# Amplificador_Clase_A.net
KiCad netlist of a schematic drawn in EAGLE
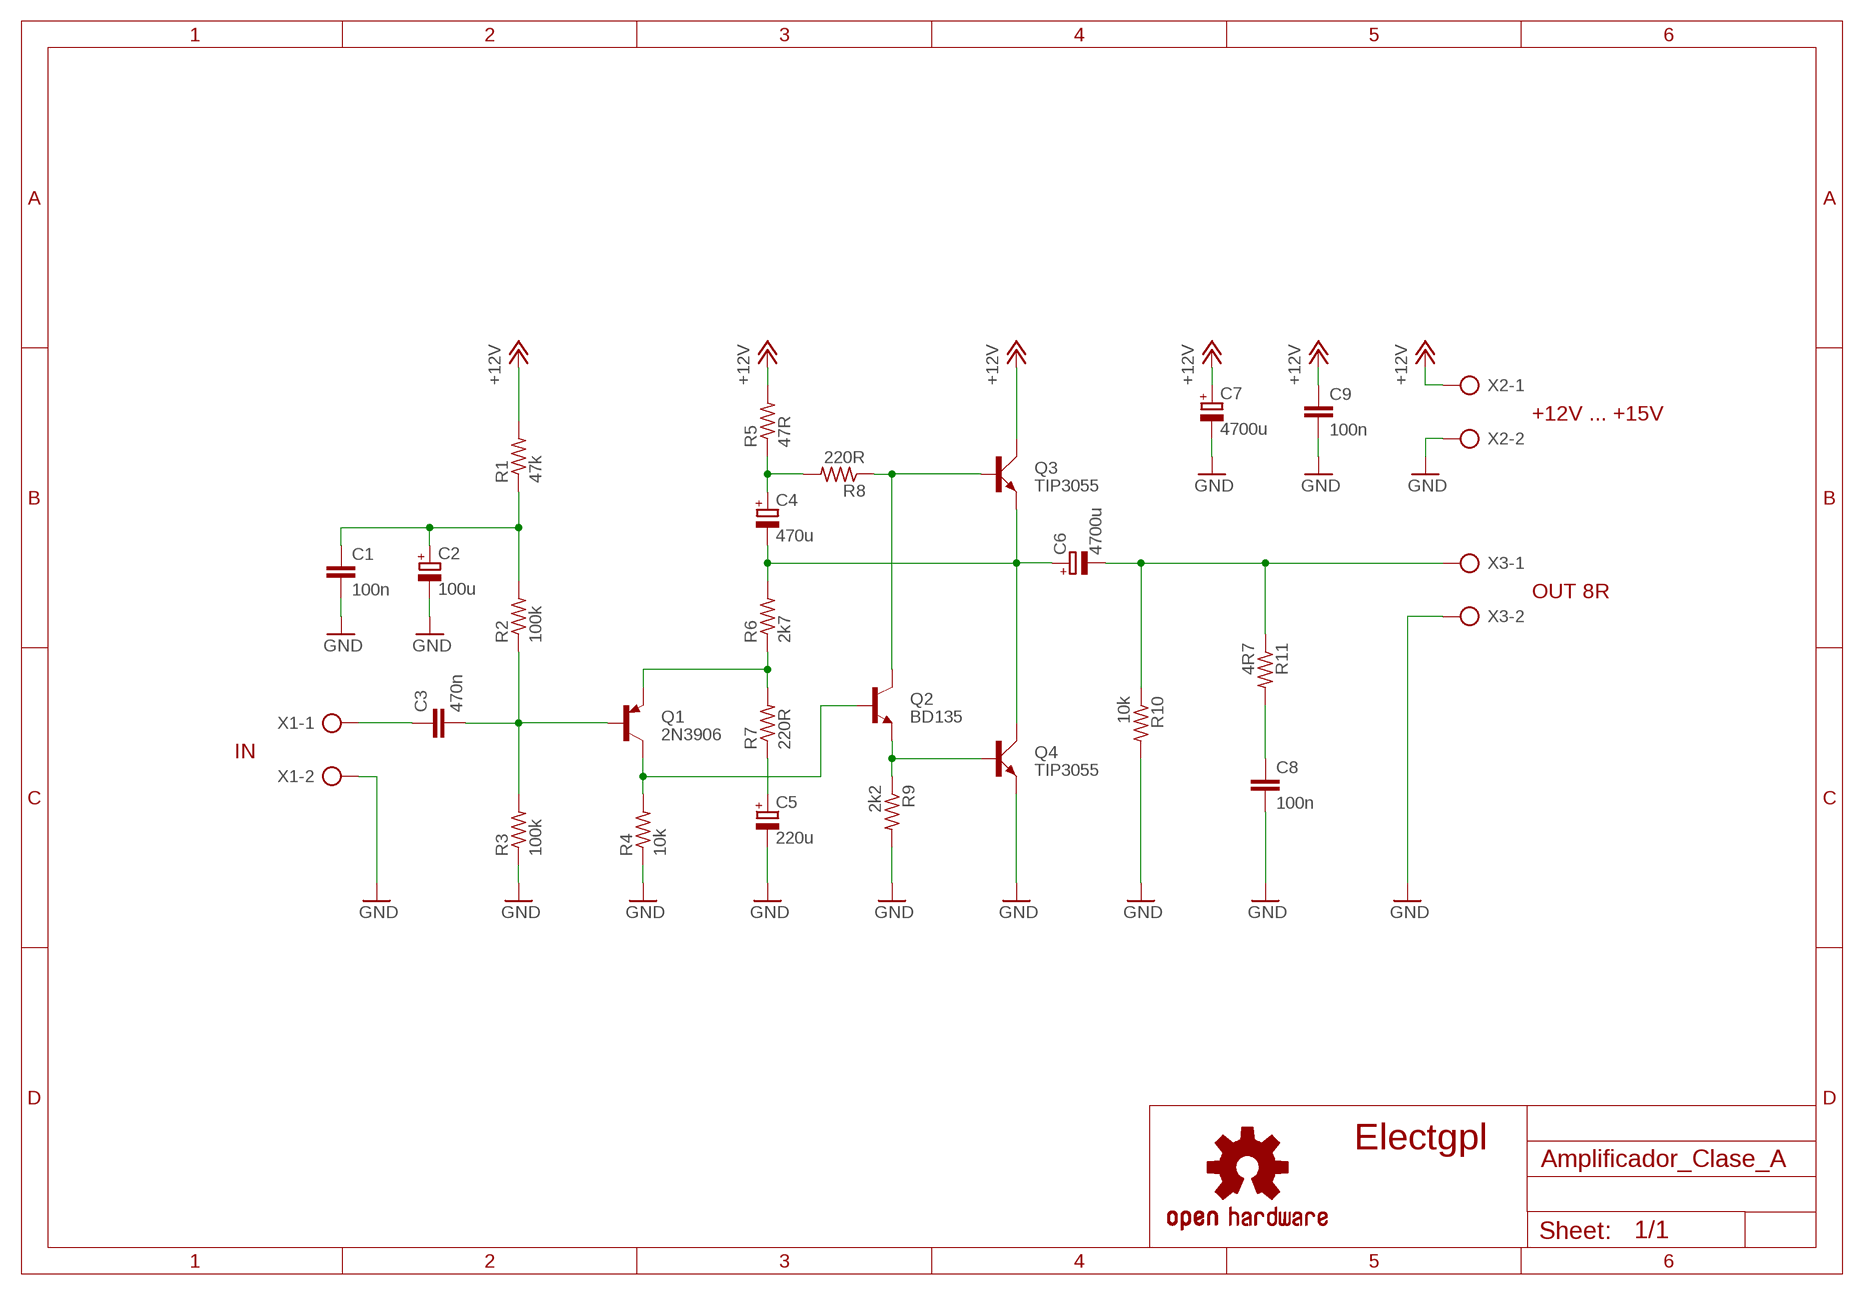
[diagram p0: schematic, sheet 1]

(export (version "E")
  (design (tool "Eeschema 10.0.6"))
  (components
    (comp (ref "C1")
      (value "100n")
      (footprint "eagle-import:C050-024X044")
      (libsource (lib "eagle-import") (part "C-EU050-024X044"))
    )
    (comp (ref "C2")
      (value "100u")
      (footprint "eagle-import:E3,5-10")
      (libsource (lib "eagle-import") (part "CPOL-EUE3.5-10"))
    )
    (comp (ref "C3")
      (value "470n")
      (footprint "eagle-import:C050-024X044")
      (libsource (lib "eagle-import") (part "C-EU050-024X044"))
    )
    (comp (ref "C4")
      (value "470u")
      (footprint "eagle-import:E7,5-16")
      (libsource (lib "eagle-import") (part "CPOL-EUE7.5-16"))
    )
    (comp (ref "C5")
      (value "220u")
      (footprint "eagle-import:E3,5-10")
      (libsource (lib "eagle-import") (part "CPOL-EUE3.5-10"))
    )
    (comp (ref "C6")
      (value "4700u")
      (footprint "eagle-import:E7,5-16")
      (libsource (lib "eagle-import") (part "CPOL-EUE7.5-16"))
    )
    (comp (ref "C7")
      (value "4700u")
      (footprint "eagle-import:E7,5-16")
      (libsource (lib "eagle-import") (part "CPOL-EUE7.5-16"))
    )
    (comp (ref "C8")
      (value "100n")
      (footprint "eagle-import:C050-024X044")
      (libsource (lib "eagle-import") (part "C-EU050-024X044"))
    )
    (comp (ref "C9")
      (value "100n")
      (footprint "eagle-import:C050-024X044")
      (libsource (lib "eagle-import") (part "C-EU050-024X044"))
    )
    (comp (ref "LOGO1")
      (value "OSHW-LOGOM")
      (footprint "eagle-import:OSHW-LOGO-M")
      (libsource (lib "eagle-import") (part "OSHW-LOGOM"))
    )
    (comp (ref "Q1")
      (value "2N3906")
      (footprint "eagle-import:TO92-EBC")
      (libsource (lib "eagle-import") (part "-PNP-TO92-EBC2N3906"))
    )
    (comp (ref "Q2")
      (value "BD135")
      (footprint "eagle-import:TO126V")
      (libsource (lib "eagle-import") (part "-NPN-TO126V"))
    )
    (comp (ref "Q3")
      (value "TIP3055")
      (footprint "eagle-import:TOP3AV")
      (libsource (lib "eagle-import") (part "TIP3055"))
    )
    (comp (ref "Q4")
      (value "TIP3055")
      (footprint "eagle-import:TOP3AV")
      (libsource (lib "eagle-import") (part "TIP3055"))
    )
    (comp (ref "R1")
      (value "47k")
      (footprint "eagle-import:0207_12")
      (libsource (lib "eagle-import") (part "R-US_0207/12"))
    )
    (comp (ref "R2")
      (value "100k")
      (footprint "eagle-import:0207_12")
      (libsource (lib "eagle-import") (part "R-US_0207/12"))
    )
    (comp (ref "R3")
      (value "100k")
      (footprint "eagle-import:0207_12")
      (libsource (lib "eagle-import") (part "R-US_0207/12"))
    )
    (comp (ref "R4")
      (value "10k")
      (footprint "eagle-import:0207_12")
      (libsource (lib "eagle-import") (part "R-US_0207/12"))
    )
    (comp (ref "R5")
      (value "47R")
      (footprint "eagle-import:0207_12")
      (libsource (lib "eagle-import") (part "R-US_0207/12"))
    )
    (comp (ref "R6")
      (value "2k7")
      (footprint "eagle-import:0207_12")
      (libsource (lib "eagle-import") (part "R-US_0207/12"))
    )
    (comp (ref "R7")
      (value "220R")
      (footprint "eagle-import:0207_12")
      (libsource (lib "eagle-import") (part "R-US_0207/12"))
    )
    (comp (ref "R8")
      (value "220R")
      (footprint "eagle-import:0207_12")
      (libsource (lib "eagle-import") (part "R-US_0207/12"))
    )
    (comp (ref "R9")
      (value "2k2")
      (footprint "eagle-import:0207_12")
      (libsource (lib "eagle-import") (part "R-US_0207/12"))
    )
    (comp (ref "R10")
      (value "10k")
      (footprint "eagle-import:0207_12")
      (libsource (lib "eagle-import") (part "R-US_0207/12"))
    )
    (comp (ref "R11")
      (value "4R7")
      (footprint "eagle-import:0207_12")
      (libsource (lib "eagle-import") (part "R-US_0207/12"))
    )
    (comp (ref "X1")
      (value "AK500/2")
      (footprint "eagle-import:AK500_2")
      (libsource (lib "eagle-import") (part "AK500/2"))
    )
    (comp (ref "X2")
      (value "AK500/2")
      (footprint "eagle-import:AK500_2")
      (libsource (lib "eagle-import") (part "AK500/2"))
    )
    (comp (ref "X3")
      (value "AK500/2")
      (footprint "eagle-import:AK500_2")
      (libsource (lib "eagle-import") (part "AK500/2"))
    )
  )
  (nets
    (net (code "1") (name "+12V") (class "Default")
      (node (ref "C7") (pin "+") (pinfunction "+_+") (pintype "passive"))
      (node (ref "C9") (pin "1") (pinfunction "1_1") (pintype "passive"))
      (node (ref "Q3") (pin "C") (pinfunction "C_C") (pintype "passive"))
      (node (ref "R1") (pin "2") (pinfunction "2_2") (pintype "passive"))
      (node (ref "R5") (pin "2") (pinfunction "2_2") (pintype "passive"))
      (node (ref "X2") (pin "1") (pinfunction "KL_1") (pintype "passive"))
    )
    (net (code "2") (name "GND") (class "Default")
      (node (ref "C1") (pin "2") (pinfunction "2_2") (pintype "passive"))
      (node (ref "C2") (pin "-") (pinfunction "-_-") (pintype "passive"))
      (node (ref "C5") (pin "-") (pinfunction "-_-") (pintype "passive"))
      (node (ref "C7") (pin "-") (pinfunction "-_-") (pintype "passive"))
      (node (ref "C8") (pin "2") (pinfunction "2_2") (pintype "passive"))
      (node (ref "C9") (pin "2") (pinfunction "2_2") (pintype "passive"))
      (node (ref "Q4") (pin "E") (pinfunction "E_E") (pintype "passive"))
      (node (ref "R10") (pin "2") (pinfunction "2_2") (pintype "passive"))
      (node (ref "R3") (pin "1") (pinfunction "1_1") (pintype "passive"))
      (node (ref "R4") (pin "1") (pinfunction "1_1") (pintype "passive"))
      (node (ref "R9") (pin "2") (pinfunction "2_2") (pintype "passive"))
      (node (ref "X1") (pin "2") (pinfunction "KL_2") (pintype "passive"))
      (node (ref "X2") (pin "2") (pinfunction "KL_2") (pintype "passive"))
      (node (ref "X3") (pin "2") (pinfunction "KL_2") (pintype "passive"))
    )
    (net (code "3") (name "Net-(C1-Pad1)") (class "Default")
      (node (ref "C1") (pin "1") (pinfunction "1_1") (pintype "passive"))
      (node (ref "C2") (pin "+") (pinfunction "+_+") (pintype "passive"))
      (node (ref "R1") (pin "1") (pinfunction "1_1") (pintype "passive"))
      (node (ref "R2") (pin "2") (pinfunction "2_2") (pintype "passive"))
    )
    (net (code "4") (name "Net-(C3-Pad2)") (class "Default")
      (node (ref "C3") (pin "2") (pinfunction "2_2") (pintype "passive"))
      (node (ref "Q1") (pin "B") (pinfunction "B_B") (pintype "passive"))
      (node (ref "R2") (pin "1") (pinfunction "1_1") (pintype "passive"))
      (node (ref "R3") (pin "2") (pinfunction "2_2") (pintype "passive"))
    )
    (net (code "5") (name "Net-(C4-Pad+)") (class "Default")
      (node (ref "C4") (pin "+") (pinfunction "+_+") (pintype "passive"))
      (node (ref "R5") (pin "1") (pinfunction "1_1") (pintype "passive"))
      (node (ref "R8") (pin "2") (pinfunction "2_2") (pintype "passive"))
    )
    (net (code "6") (name "Net-(C4-Pad-)") (class "Default")
      (node (ref "C4") (pin "-") (pinfunction "-_-") (pintype "passive"))
      (node (ref "C6") (pin "+") (pinfunction "+_+") (pintype "passive"))
      (node (ref "Q3") (pin "E") (pinfunction "E_E") (pintype "passive"))
      (node (ref "Q4") (pin "C") (pinfunction "C_C") (pintype "passive"))
      (node (ref "R6") (pin "2") (pinfunction "2_2") (pintype "passive"))
    )
    (net (code "7") (name "Net-(C5-Pad+)") (class "Default")
      (node (ref "C5") (pin "+") (pinfunction "+_+") (pintype "passive"))
      (node (ref "R7") (pin "1") (pinfunction "1_1") (pintype "passive"))
    )
    (net (code "8") (name "Net-(C8-Pad1)") (class "Default")
      (node (ref "C8") (pin "1") (pinfunction "1_1") (pintype "passive"))
      (node (ref "R11") (pin "2") (pinfunction "2_2") (pintype "passive"))
    )
    (net (code "9") (name "Net-(Q1-PadE)") (class "Default")
      (node (ref "Q1") (pin "E") (pinfunction "E_E") (pintype "passive"))
      (node (ref "R6") (pin "1") (pinfunction "1_1") (pintype "passive"))
      (node (ref "R7") (pin "2") (pinfunction "2_2") (pintype "passive"))
    )
    (net (code "10") (name "Net-(Q2-B)") (class "Default")
      (node (ref "Q1") (pin "C") (pinfunction "C_C") (pintype "passive"))
      (node (ref "Q2") (pin "3") (pinfunction "B_3") (pintype "passive"))
      (node (ref "R4") (pin "2") (pinfunction "2_2") (pintype "passive"))
    )
    (net (code "11") (name "Net-(Q2-C)") (class "Default")
      (node (ref "Q2") (pin "2") (pinfunction "C_2") (pintype "passive"))
      (node (ref "Q3") (pin "B") (pinfunction "B_B") (pintype "passive"))
      (node (ref "R8") (pin "1") (pinfunction "1_1") (pintype "passive"))
    )
    (net (code "12") (name "Net-(Q2-E)") (class "Default")
      (node (ref "Q2") (pin "1") (pinfunction "E_1") (pintype "passive"))
      (node (ref "Q4") (pin "B") (pinfunction "B_B") (pintype "passive"))
      (node (ref "R9") (pin "1") (pinfunction "1_1") (pintype "passive"))
    )
    (net (code "13") (name "Net-(X1A-KL)") (class "Default")
      (node (ref "C3") (pin "1") (pinfunction "1_1") (pintype "passive"))
      (node (ref "X1") (pin "1") (pinfunction "KL_1") (pintype "passive"))
    )
    (net (code "14") (name "Net-(X3A-KL)") (class "Default")
      (node (ref "C6") (pin "-") (pinfunction "-_-") (pintype "passive"))
      (node (ref "R10") (pin "1") (pinfunction "1_1") (pintype "passive"))
      (node (ref "R11") (pin "1") (pinfunction "1_1") (pintype "passive"))
      (node (ref "X3") (pin "1") (pinfunction "KL_1") (pintype "passive"))
    )
  )
)
